# R201B.net
KiCad netlist of a schematic drawn in EAGLE
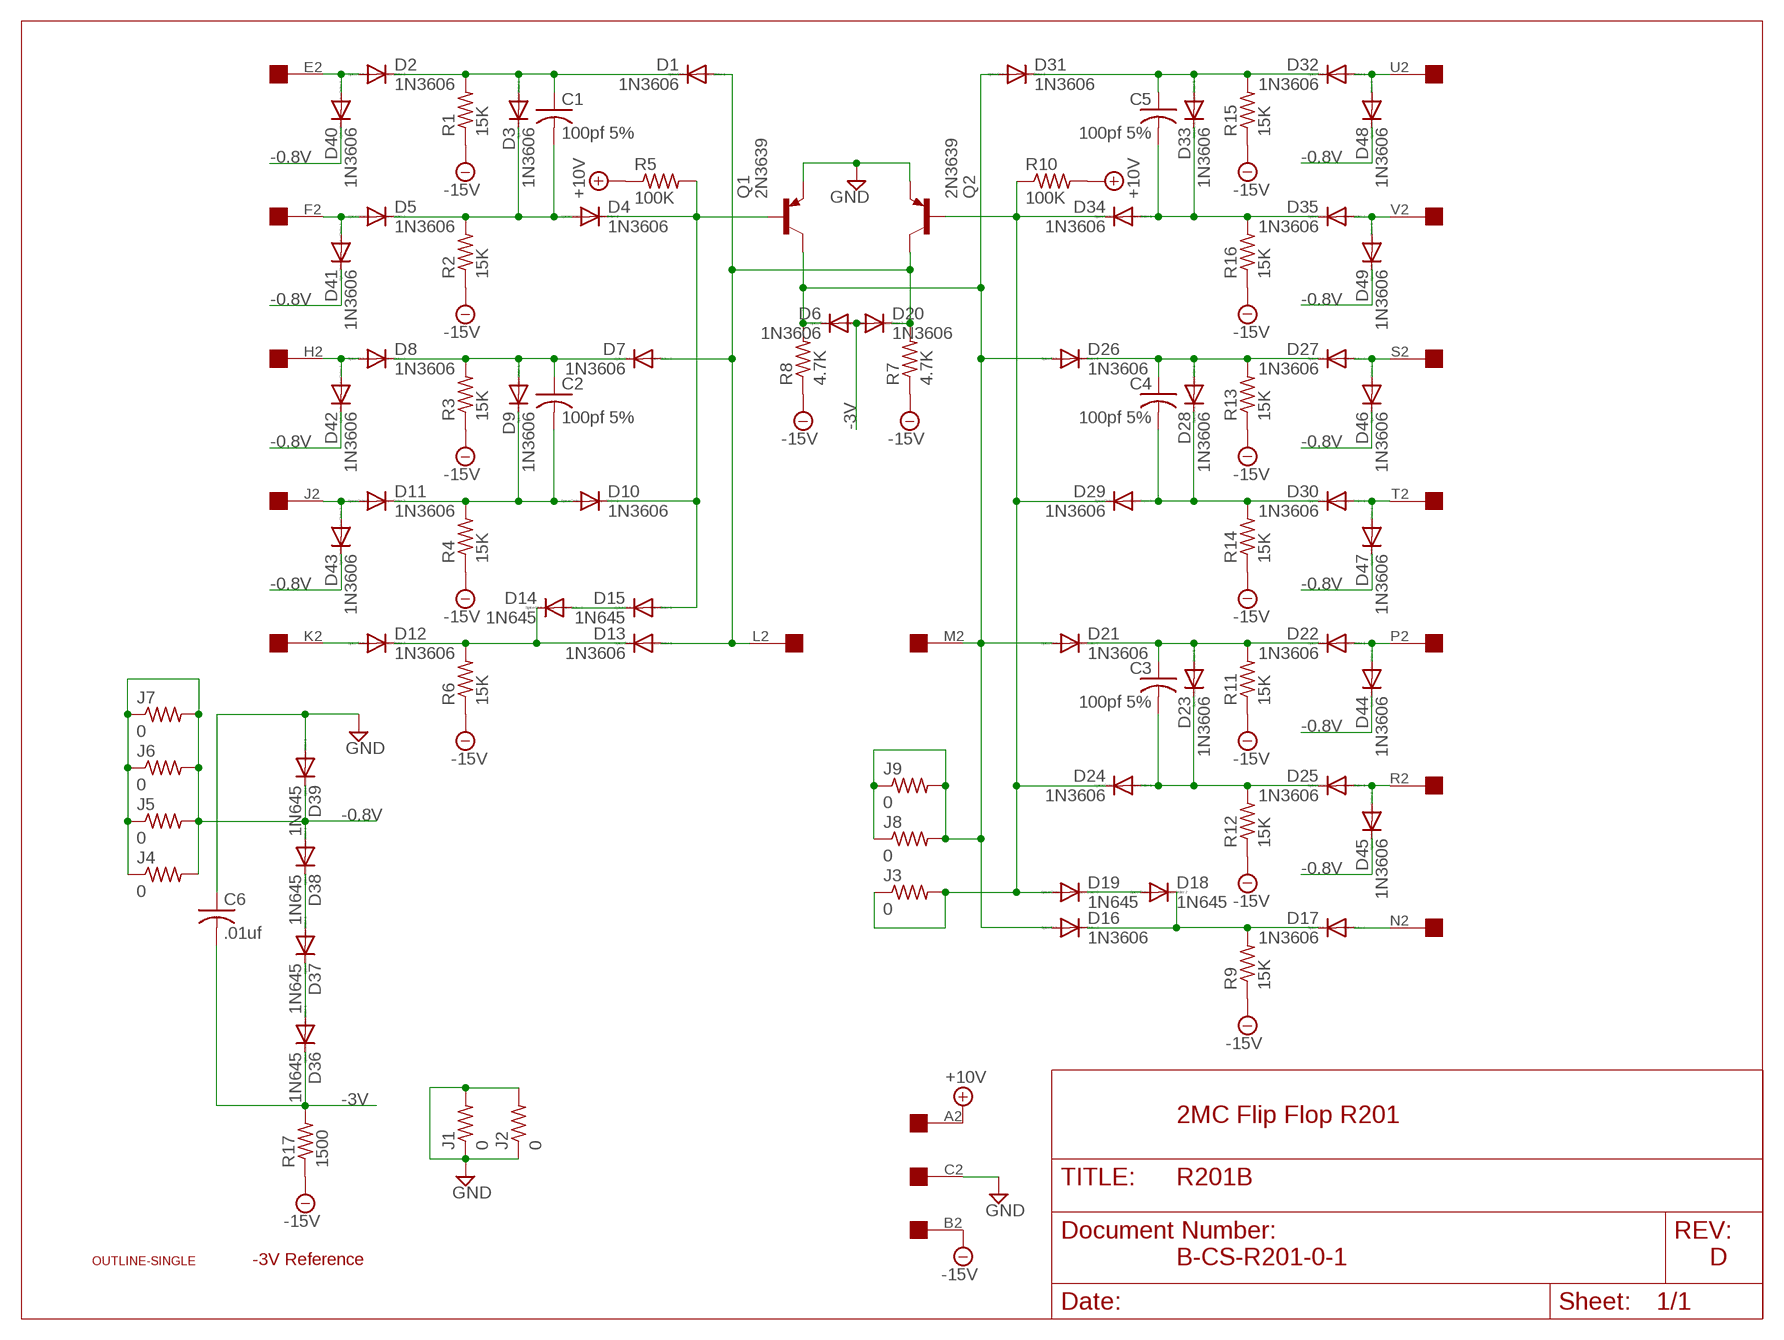
[diagram p0: schematic, sheet 1]

(export (version "E")
  (design (tool "Eeschema 10.0.6"))
  (components
    (comp (ref "C1")
      (value "100pf 5%")
      (footprint "eagle-import:C063-025X075")
      (libsource (lib "eagle-import") (part "C-US"))
    )
    (comp (ref "C2")
      (value "100pf 5%")
      (footprint "eagle-import:C063-025X075")
      (libsource (lib "eagle-import") (part "C-US"))
    )
    (comp (ref "C3")
      (value "100pf 5%")
      (footprint "eagle-import:C063-025X075")
      (libsource (lib "eagle-import") (part "C-US"))
    )
    (comp (ref "C4")
      (value "100pf 5%")
      (footprint "eagle-import:C063-025X075")
      (libsource (lib "eagle-import") (part "C-US"))
    )
    (comp (ref "C5")
      (value "100pf 5%")
      (footprint "eagle-import:C063-025X075")
      (libsource (lib "eagle-import") (part "C-US"))
    )
    (comp (ref "C6")
      (value ".01uf")
      (footprint "eagle-import:C063-025X075")
      (libsource (lib "eagle-import") (part "C-US"))
    )
    (comp (ref "D1")
      (value "1N3606")
      (footprint "eagle-import:DO35-10")
      (libsource (lib "eagle-import") (part "1N4148DO35-10"))
    )
    (comp (ref "D2")
      (value "1N3606")
      (footprint "eagle-import:DO35-10")
      (libsource (lib "eagle-import") (part "1N4148DO35-10"))
    )
    (comp (ref "D3")
      (value "1N3606")
      (footprint "eagle-import:DO35-10")
      (libsource (lib "eagle-import") (part "1N4148DO35-10"))
    )
    (comp (ref "D4")
      (value "1N3606")
      (footprint "eagle-import:DO35-10")
      (libsource (lib "eagle-import") (part "1N4148DO35-10"))
    )
    (comp (ref "D5")
      (value "1N3606")
      (footprint "eagle-import:DO35-10")
      (libsource (lib "eagle-import") (part "1N4148DO35-10"))
    )
    (comp (ref "D6")
      (value "1N3606")
      (footprint "eagle-import:DO35-10")
      (libsource (lib "eagle-import") (part "1N4148DO35-10"))
    )
    (comp (ref "D7")
      (value "1N3606")
      (footprint "eagle-import:DO35-10")
      (libsource (lib "eagle-import") (part "1N4148DO35-10"))
    )
    (comp (ref "D8")
      (value "1N3606")
      (footprint "eagle-import:DO35-10")
      (libsource (lib "eagle-import") (part "1N4148DO35-10"))
    )
    (comp (ref "D9")
      (value "1N3606")
      (footprint "eagle-import:DO35-10")
      (libsource (lib "eagle-import") (part "1N4148DO35-10"))
    )
    (comp (ref "D10")
      (value "1N3606")
      (footprint "eagle-import:DO35-10")
      (libsource (lib "eagle-import") (part "1N4148DO35-10"))
    )
    (comp (ref "D11")
      (value "1N3606")
      (footprint "eagle-import:DO35-10")
      (libsource (lib "eagle-import") (part "1N4148DO35-10"))
    )
    (comp (ref "D12")
      (value "1N3606")
      (footprint "eagle-import:DO35-10")
      (libsource (lib "eagle-import") (part "1N4148DO35-10"))
    )
    (comp (ref "D13")
      (value "1N3606")
      (footprint "eagle-import:DO35-10")
      (libsource (lib "eagle-import") (part "1N4148DO35-10"))
    )
    (comp (ref "D14")
      (value "1N645")
      (footprint "eagle-import:DO35-10")
      (libsource (lib "eagle-import") (part "1N4148DO35-10"))
    )
    (comp (ref "D15")
      (value "1N645")
      (footprint "eagle-import:DO35-10")
      (libsource (lib "eagle-import") (part "1N4148DO35-10"))
    )
    (comp (ref "D16")
      (value "1N3606")
      (footprint "eagle-import:DO35-10")
      (libsource (lib "eagle-import") (part "1N4148DO35-10"))
    )
    (comp (ref "D17")
      (value "1N3606")
      (footprint "eagle-import:DO35-10")
      (libsource (lib "eagle-import") (part "1N4148DO35-10"))
    )
    (comp (ref "D18")
      (value "1N645")
      (footprint "eagle-import:DO35-10")
      (libsource (lib "eagle-import") (part "1N4148DO35-10"))
    )
    (comp (ref "D19")
      (value "1N645")
      (footprint "eagle-import:DO35-10")
      (libsource (lib "eagle-import") (part "1N4148DO35-10"))
    )
    (comp (ref "D20")
      (value "1N3606")
      (footprint "eagle-import:DO35-10")
      (libsource (lib "eagle-import") (part "1N4148DO35-10"))
    )
    (comp (ref "D21")
      (value "1N3606")
      (footprint "eagle-import:DO35-10")
      (libsource (lib "eagle-import") (part "1N4148DO35-10"))
    )
    (comp (ref "D22")
      (value "1N3606")
      (footprint "eagle-import:DO35-10")
      (libsource (lib "eagle-import") (part "1N4148DO35-10"))
    )
    (comp (ref "D23")
      (value "1N3606")
      (footprint "eagle-import:DO35-10")
      (libsource (lib "eagle-import") (part "1N4148DO35-10"))
    )
    (comp (ref "D24")
      (value "1N3606")
      (footprint "eagle-import:DO35-10")
      (libsource (lib "eagle-import") (part "1N4148DO35-10"))
    )
    (comp (ref "D25")
      (value "1N3606")
      (footprint "eagle-import:DO35-10")
      (libsource (lib "eagle-import") (part "1N4148DO35-10"))
    )
    (comp (ref "D26")
      (value "1N3606")
      (footprint "eagle-import:DO35-10")
      (libsource (lib "eagle-import") (part "1N4148DO35-10"))
    )
    (comp (ref "D27")
      (value "1N3606")
      (footprint "eagle-import:DO35-10")
      (libsource (lib "eagle-import") (part "1N4148DO35-10"))
    )
    (comp (ref "D28")
      (value "1N3606")
      (footprint "eagle-import:DO35-10")
      (libsource (lib "eagle-import") (part "1N4148DO35-10"))
    )
    (comp (ref "D29")
      (value "1N3606")
      (footprint "eagle-import:DO35-10")
      (libsource (lib "eagle-import") (part "1N4148DO35-10"))
    )
    (comp (ref "D30")
      (value "1N3606")
      (footprint "eagle-import:DO35-10")
      (libsource (lib "eagle-import") (part "1N4148DO35-10"))
    )
    (comp (ref "D31")
      (value "1N3606")
      (footprint "eagle-import:DO35-10")
      (libsource (lib "eagle-import") (part "1N4148DO35-10"))
    )
    (comp (ref "D32")
      (value "1N3606")
      (footprint "eagle-import:DO35-10")
      (libsource (lib "eagle-import") (part "1N4148DO35-10"))
    )
    (comp (ref "D33")
      (value "1N3606")
      (footprint "eagle-import:DO35-10")
      (libsource (lib "eagle-import") (part "1N4148DO35-10"))
    )
    (comp (ref "D34")
      (value "1N3606")
      (footprint "eagle-import:DO35-10")
      (libsource (lib "eagle-import") (part "1N4148DO35-10"))
    )
    (comp (ref "D35")
      (value "1N3606")
      (footprint "eagle-import:DO35-10")
      (libsource (lib "eagle-import") (part "1N4148DO35-10"))
    )
    (comp (ref "D36")
      (value "1N645")
      (footprint "eagle-import:DO35-10")
      (libsource (lib "eagle-import") (part "1N4148DO35-10"))
    )
    (comp (ref "D37")
      (value "1N645")
      (footprint "eagle-import:DO35-10")
      (libsource (lib "eagle-import") (part "1N4148DO35-10"))
    )
    (comp (ref "D38")
      (value "1N645")
      (footprint "eagle-import:DO35-10")
      (libsource (lib "eagle-import") (part "1N4148DO35-10"))
    )
    (comp (ref "D39")
      (value "1N645")
      (footprint "eagle-import:DO35-10")
      (libsource (lib "eagle-import") (part "1N4148DO35-10"))
    )
    (comp (ref "D40")
      (value "1N3606")
      (footprint "eagle-import:DO35-10")
      (libsource (lib "eagle-import") (part "1N4148DO35-10"))
    )
    (comp (ref "D41")
      (value "1N3606")
      (footprint "eagle-import:DO35-10")
      (libsource (lib "eagle-import") (part "1N4148DO35-10"))
    )
    (comp (ref "D42")
      (value "1N3606")
      (footprint "eagle-import:DO35-10")
      (libsource (lib "eagle-import") (part "1N4148DO35-10"))
    )
    (comp (ref "D43")
      (value "1N3606")
      (footprint "eagle-import:DO35-10")
      (libsource (lib "eagle-import") (part "1N4148DO35-10"))
    )
    (comp (ref "D44")
      (value "1N3606")
      (footprint "eagle-import:DO35-10")
      (libsource (lib "eagle-import") (part "1N4148DO35-10"))
    )
    (comp (ref "D45")
      (value "1N3606")
      (footprint "eagle-import:DO35-10")
      (libsource (lib "eagle-import") (part "1N4148DO35-10"))
    )
    (comp (ref "D46")
      (value "1N3606")
      (footprint "eagle-import:DO35-10")
      (libsource (lib "eagle-import") (part "1N4148DO35-10"))
    )
    (comp (ref "D47")
      (value "1N3606")
      (footprint "eagle-import:DO35-10")
      (libsource (lib "eagle-import") (part "1N4148DO35-10"))
    )
    (comp (ref "D48")
      (value "1N3606")
      (footprint "eagle-import:DO35-10")
      (libsource (lib "eagle-import") (part "1N4148DO35-10"))
    )
    (comp (ref "D49")
      (value "1N3606")
      (footprint "eagle-import:DO35-10")
      (libsource (lib "eagle-import") (part "1N4148DO35-10"))
    )
    (comp (ref "J1")
      (value "0")
      (footprint "eagle-import:0207_10")
      (libsource (lib "eagle-import") (part "R-US_0207/10"))
    )
    (comp (ref "J2")
      (value "0")
      (footprint "eagle-import:0207_10")
      (libsource (lib "eagle-import") (part "R-US_0207/10"))
    )
    (comp (ref "J3")
      (value "0")
      (footprint "eagle-import:0207_10")
      (libsource (lib "eagle-import") (part "R-US_0207/10"))
    )
    (comp (ref "J4")
      (value "0")
      (footprint "eagle-import:0207_10")
      (libsource (lib "eagle-import") (part "R-US_0207/10"))
    )
    (comp (ref "J5")
      (value "0")
      (footprint "eagle-import:0207_10")
      (libsource (lib "eagle-import") (part "R-US_0207/10"))
    )
    (comp (ref "J6")
      (value "0")
      (footprint "eagle-import:0207_10")
      (libsource (lib "eagle-import") (part "R-US_0207/10"))
    )
    (comp (ref "J7")
      (value "0")
      (footprint "eagle-import:0207_10")
      (libsource (lib "eagle-import") (part "R-US_0207/10"))
    )
    (comp (ref "J8")
      (value "0")
      (footprint "eagle-import:0207_10")
      (libsource (lib "eagle-import") (part "R-US_0207/10"))
    )
    (comp (ref "J9")
      (value "0")
      (footprint "eagle-import:0207_10")
      (libsource (lib "eagle-import") (part "R-US_0207/10"))
    )
    (comp (ref "Q1")
      (value "2N3639")
      (footprint "eagle-import:TO39")
      (libsource (lib "eagle-import") (part "2N3637"))
    )
    (comp (ref "Q2")
      (value "2N3639")
      (footprint "eagle-import:TO39")
      (libsource (lib "eagle-import") (part "2N3637"))
    )
    (comp (ref "R1")
      (value "15K")
      (footprint "eagle-import:0207_10")
      (libsource (lib "eagle-import") (part "R-US_0207/10"))
    )
    (comp (ref "R2")
      (value "15K")
      (footprint "eagle-import:0207_10")
      (libsource (lib "eagle-import") (part "R-US_0207/10"))
    )
    (comp (ref "R3")
      (value "15K")
      (footprint "eagle-import:0207_10")
      (libsource (lib "eagle-import") (part "R-US_0207/10"))
    )
    (comp (ref "R4")
      (value "15K")
      (footprint "eagle-import:0207_10")
      (libsource (lib "eagle-import") (part "R-US_0207/10"))
    )
    (comp (ref "R5")
      (value "100K")
      (footprint "eagle-import:0207_10")
      (libsource (lib "eagle-import") (part "R-US_0207/10"))
    )
    (comp (ref "R6")
      (value "15K")
      (footprint "eagle-import:0207_10")
      (libsource (lib "eagle-import") (part "R-US_0207/10"))
    )
    (comp (ref "R7")
      (value "4.7K")
      (footprint "eagle-import:0207_10")
      (libsource (lib "eagle-import") (part "R-US_0207/10"))
    )
    (comp (ref "R8")
      (value "4.7K")
      (footprint "eagle-import:0207_10")
      (libsource (lib "eagle-import") (part "R-US_0207/10"))
    )
    (comp (ref "R9")
      (value "15K")
      (footprint "eagle-import:0207_10")
      (libsource (lib "eagle-import") (part "R-US_0207/10"))
    )
    (comp (ref "R10")
      (value "100K")
      (footprint "eagle-import:0207_10")
      (libsource (lib "eagle-import") (part "R-US_0207/10"))
    )
    (comp (ref "R11")
      (value "15K")
      (footprint "eagle-import:0207_10")
      (libsource (lib "eagle-import") (part "R-US_0207/10"))
    )
    (comp (ref "R12")
      (value "15K")
      (footprint "eagle-import:0207_10")
      (libsource (lib "eagle-import") (part "R-US_0207/10"))
    )
    (comp (ref "R13")
      (value "15K")
      (footprint "eagle-import:0207_10")
      (libsource (lib "eagle-import") (part "R-US_0207/10"))
    )
    (comp (ref "R14")
      (value "15K")
      (footprint "eagle-import:0207_10")
      (libsource (lib "eagle-import") (part "R-US_0207/10"))
    )
    (comp (ref "R15")
      (value "15K")
      (footprint "eagle-import:0207_10")
      (libsource (lib "eagle-import") (part "R-US_0207/10"))
    )
    (comp (ref "R16")
      (value "15K")
      (footprint "eagle-import:0207_10")
      (libsource (lib "eagle-import") (part "R-US_0207/10"))
    )
    (comp (ref "R17")
      (value "1500")
      (footprint "eagle-import:0207_10")
      (libsource (lib "eagle-import") (part "R-US_0207/10"))
    )
    (comp (ref "U$1")
      (value "OUTLINE-SINGLE")
      (footprint "eagle-import:SINGLE")
      (libsource (lib "eagle-import") (part "OUTLINE-SINGLE"))
    )
    (comp (ref "U$2")
      (value "EDGE-1")
      (footprint "eagle-import:EDGE-CON1")
      (libsource (lib "eagle-import") (part "EDGE-1"))
    )
  )
  (nets
    (net (code "1") (name "+10V") (class "Default")
      (node (ref "R10") (pin "2") (pinfunction "2_2") (pintype "passive"))
      (node (ref "R5") (pin "1") (pinfunction "1_1") (pintype "passive"))
      (node (ref "U$2") (pin "A2") (pinfunction "1_A2") (pintype "bidirectional"))
    )
    (net (code "2") (name "-15V") (class "Default")
      (node (ref "R1") (pin "1") (pinfunction "1_1") (pintype "passive"))
      (node (ref "R11") (pin "1") (pinfunction "1_1") (pintype "passive"))
      (node (ref "R12") (pin "1") (pinfunction "1_1") (pintype "passive"))
      (node (ref "R13") (pin "1") (pinfunction "1_1") (pintype "passive"))
      (node (ref "R14") (pin "1") (pinfunction "1_1") (pintype "passive"))
      (node (ref "R15") (pin "1") (pinfunction "1_1") (pintype "passive"))
      (node (ref "R16") (pin "1") (pinfunction "1_1") (pintype "passive"))
      (node (ref "R17") (pin "1") (pinfunction "1_1") (pintype "passive"))
      (node (ref "R2") (pin "1") (pinfunction "1_1") (pintype "passive"))
      (node (ref "R3") (pin "1") (pinfunction "1_1") (pintype "passive"))
      (node (ref "R4") (pin "1") (pinfunction "1_1") (pintype "passive"))
      (node (ref "R6") (pin "1") (pinfunction "1_1") (pintype "passive"))
      (node (ref "R7") (pin "1") (pinfunction "1_1") (pintype "passive"))
      (node (ref "R8") (pin "1") (pinfunction "1_1") (pintype "passive"))
      (node (ref "R9") (pin "1") (pinfunction "1_1") (pintype "passive"))
      (node (ref "U$2") (pin "B2") (pinfunction "1_B2") (pintype "bidirectional"))
    )
    (net (code "3") (name "/-0.8V") (class "Default")
      (node (ref "D38") (pin "A") (pinfunction "A_A") (pintype "passive"))
      (node (ref "D39") (pin "C") (pinfunction "C_C") (pintype "passive"))
      (node (ref "D40") (pin "C") (pinfunction "C_C") (pintype "passive"))
      (node (ref "D41") (pin "C") (pinfunction "C_C") (pintype "passive"))
      (node (ref "D42") (pin "C") (pinfunction "C_C") (pintype "passive"))
      (node (ref "D43") (pin "C") (pinfunction "C_C") (pintype "passive"))
      (node (ref "D44") (pin "C") (pinfunction "C_C") (pintype "passive"))
      (node (ref "D45") (pin "C") (pinfunction "C_C") (pintype "passive"))
      (node (ref "D46") (pin "C") (pinfunction "C_C") (pintype "passive"))
      (node (ref "D47") (pin "C") (pinfunction "C_C") (pintype "passive"))
      (node (ref "D48") (pin "C") (pinfunction "C_C") (pintype "passive"))
      (node (ref "D49") (pin "C") (pinfunction "C_C") (pintype "passive"))
      (node (ref "J4") (pin "1") (pinfunction "1_1") (pintype "passive"))
      (node (ref "J4") (pin "2") (pinfunction "2_2") (pintype "passive"))
      (node (ref "J5") (pin "1") (pinfunction "1_1") (pintype "passive"))
      (node (ref "J5") (pin "2") (pinfunction "2_2") (pintype "passive"))
      (node (ref "J6") (pin "1") (pinfunction "1_1") (pintype "passive"))
      (node (ref "J6") (pin "2") (pinfunction "2_2") (pintype "passive"))
      (node (ref "J7") (pin "1") (pinfunction "1_1") (pintype "passive"))
      (node (ref "J7") (pin "2") (pinfunction "2_2") (pintype "passive"))
    )
    (net (code "4") (name "/-3V") (class "Default")
      (node (ref "C6") (pin "2") (pinfunction "2_2") (pintype "passive"))
      (node (ref "D20") (pin "A") (pinfunction "A_A") (pintype "passive"))
      (node (ref "D36") (pin "C") (pinfunction "C_C") (pintype "passive"))
      (node (ref "D6") (pin "A") (pinfunction "A_A") (pintype "passive"))
      (node (ref "R17") (pin "2") (pinfunction "2_2") (pintype "passive"))
    )
    (net (code "5") (name "GND") (class "Default")
      (node (ref "C6") (pin "1") (pinfunction "1_1") (pintype "passive"))
      (node (ref "D39") (pin "A") (pinfunction "A_A") (pintype "passive"))
      (node (ref "J1") (pin "1") (pinfunction "1_1") (pintype "passive"))
      (node (ref "J1") (pin "2") (pinfunction "2_2") (pintype "passive"))
      (node (ref "J2") (pin "1") (pinfunction "1_1") (pintype "passive"))
      (node (ref "J2") (pin "2") (pinfunction "2_2") (pintype "passive"))
      (node (ref "Q1") (pin "1") (pinfunction "E_1") (pintype "passive"))
      (node (ref "Q2") (pin "1") (pinfunction "E_1") (pintype "passive"))
      (node (ref "U$2") (pin "C2") (pinfunction "1_C2") (pintype "bidirectional"))
    )
    (net (code "6") (name "Net-(C1-Pad1)") (class "Default")
      (node (ref "C1") (pin "1") (pinfunction "1_1") (pintype "passive"))
      (node (ref "D1") (pin "C") (pinfunction "C_C") (pintype "passive"))
      (node (ref "D2") (pin "C") (pinfunction "C_C") (pintype "passive"))
      (node (ref "D3") (pin "A") (pinfunction "A_A") (pintype "passive"))
      (node (ref "R1") (pin "2") (pinfunction "2_2") (pintype "passive"))
    )
    (net (code "7") (name "Net-(C1-Pad2)") (class "Default")
      (node (ref "C1") (pin "2") (pinfunction "2_2") (pintype "passive"))
      (node (ref "D3") (pin "C") (pinfunction "C_C") (pintype "passive"))
      (node (ref "D4") (pin "A") (pinfunction "A_A") (pintype "passive"))
      (node (ref "D5") (pin "C") (pinfunction "C_C") (pintype "passive"))
      (node (ref "R2") (pin "2") (pinfunction "2_2") (pintype "passive"))
    )
    (net (code "8") (name "Net-(C2-Pad1)") (class "Default")
      (node (ref "C2") (pin "1") (pinfunction "1_1") (pintype "passive"))
      (node (ref "D7") (pin "C") (pinfunction "C_C") (pintype "passive"))
      (node (ref "D8") (pin "C") (pinfunction "C_C") (pintype "passive"))
      (node (ref "D9") (pin "A") (pinfunction "A_A") (pintype "passive"))
      (node (ref "R3") (pin "2") (pinfunction "2_2") (pintype "passive"))
    )
    (net (code "9") (name "Net-(C2-Pad2)") (class "Default")
      (node (ref "C2") (pin "2") (pinfunction "2_2") (pintype "passive"))
      (node (ref "D10") (pin "A") (pinfunction "A_A") (pintype "passive"))
      (node (ref "D11") (pin "C") (pinfunction "C_C") (pintype "passive"))
      (node (ref "D9") (pin "C") (pinfunction "C_C") (pintype "passive"))
      (node (ref "R4") (pin "2") (pinfunction "2_2") (pintype "passive"))
    )
    (net (code "10") (name "Net-(C3-Pad1)") (class "Default")
      (node (ref "C3") (pin "1") (pinfunction "1_1") (pintype "passive"))
      (node (ref "D21") (pin "C") (pinfunction "C_C") (pintype "passive"))
      (node (ref "D22") (pin "C") (pinfunction "C_C") (pintype "passive"))
      (node (ref "D23") (pin "A") (pinfunction "A_A") (pintype "passive"))
      (node (ref "R11") (pin "2") (pinfunction "2_2") (pintype "passive"))
    )
    (net (code "11") (name "Net-(C3-Pad2)") (class "Default")
      (node (ref "C3") (pin "2") (pinfunction "2_2") (pintype "passive"))
      (node (ref "D23") (pin "C") (pinfunction "C_C") (pintype "passive"))
      (node (ref "D24") (pin "A") (pinfunction "A_A") (pintype "passive"))
      (node (ref "D25") (pin "C") (pinfunction "C_C") (pintype "passive"))
      (node (ref "R12") (pin "2") (pinfunction "2_2") (pintype "passive"))
    )
    (net (code "12") (name "Net-(C4-Pad1)") (class "Default")
      (node (ref "C4") (pin "1") (pinfunction "1_1") (pintype "passive"))
      (node (ref "D26") (pin "C") (pinfunction "C_C") (pintype "passive"))
      (node (ref "D27") (pin "C") (pinfunction "C_C") (pintype "passive"))
      (node (ref "D28") (pin "A") (pinfunction "A_A") (pintype "passive"))
      (node (ref "R13") (pin "2") (pinfunction "2_2") (pintype "passive"))
    )
    (net (code "13") (name "Net-(C4-Pad2)") (class "Default")
      (node (ref "C4") (pin "2") (pinfunction "2_2") (pintype "passive"))
      (node (ref "D28") (pin "C") (pinfunction "C_C") (pintype "passive"))
      (node (ref "D29") (pin "A") (pinfunction "A_A") (pintype "passive"))
      (node (ref "D30") (pin "C") (pinfunction "C_C") (pintype "passive"))
      (node (ref "R14") (pin "2") (pinfunction "2_2") (pintype "passive"))
    )
    (net (code "14") (name "Net-(C5-Pad1)") (class "Default")
      (node (ref "C5") (pin "1") (pinfunction "1_1") (pintype "passive"))
      (node (ref "D31") (pin "C") (pinfunction "C_C") (pintype "passive"))
      (node (ref "D32") (pin "C") (pinfunction "C_C") (pintype "passive"))
      (node (ref "D33") (pin "A") (pinfunction "A_A") (pintype "passive"))
      (node (ref "R15") (pin "2") (pinfunction "2_2") (pintype "passive"))
    )
    (net (code "15") (name "Net-(C5-Pad2)") (class "Default")
      (node (ref "C5") (pin "2") (pinfunction "2_2") (pintype "passive"))
      (node (ref "D33") (pin "C") (pinfunction "C_C") (pintype "passive"))
      (node (ref "D34") (pin "A") (pinfunction "A_A") (pintype "passive"))
      (node (ref "D35") (pin "C") (pinfunction "C_C") (pintype "passive"))
      (node (ref "R16") (pin "2") (pinfunction "2_2") (pintype "passive"))
    )
    (net (code "16") (name "Net-(D12-PadC)") (class "Default")
      (node (ref "D12") (pin "C") (pinfunction "C_C") (pintype "passive"))
      (node (ref "D13") (pin "C") (pinfunction "C_C") (pintype "passive"))
      (node (ref "D14") (pin "C") (pinfunction "C_C") (pintype "passive"))
      (node (ref "R6") (pin "2") (pinfunction "2_2") (pintype "passive"))
    )
    (net (code "17") (name "Net-(D14-PadA)") (class "Default")
      (node (ref "D14") (pin "A") (pinfunction "A_A") (pintype "passive"))
      (node (ref "D15") (pin "C") (pinfunction "C_C") (pintype "passive"))
    )
    (net (code "18") (name "Net-(D16-PadC)") (class "Default")
      (node (ref "D16") (pin "C") (pinfunction "C_C") (pintype "passive"))
      (node (ref "D17") (pin "C") (pinfunction "C_C") (pintype "passive"))
      (node (ref "D18") (pin "C") (pinfunction "C_C") (pintype "passive"))
      (node (ref "R9") (pin "2") (pinfunction "2_2") (pintype "passive"))
    )
    (net (code "19") (name "Net-(D18-PadA)") (class "Default")
      (node (ref "D18") (pin "A") (pinfunction "A_A") (pintype "passive"))
      (node (ref "D19") (pin "C") (pinfunction "C_C") (pintype "passive"))
    )
    (net (code "20") (name "Net-(D36-PadA)") (class "Default")
      (node (ref "D36") (pin "A") (pinfunction "A_A") (pintype "passive"))
      (node (ref "D37") (pin "C") (pinfunction "C_C") (pintype "passive"))
    )
    (net (code "21") (name "Net-(D37-PadA)") (class "Default")
      (node (ref "D37") (pin "A") (pinfunction "A_A") (pintype "passive"))
      (node (ref "D38") (pin "C") (pinfunction "C_C") (pintype "passive"))
    )
    (net (code "22") (name "Net-(Q1-B)") (class "Default")
      (node (ref "D10") (pin "C") (pinfunction "C_C") (pintype "passive"))
      (node (ref "D15") (pin "A") (pinfunction "A_A") (pintype "passive"))
      (node (ref "D4") (pin "C") (pinfunction "C_C") (pintype "passive"))
      (node (ref "Q1") (pin "2") (pinfunction "B_2") (pintype "passive"))
      (node (ref "R5") (pin "2") (pinfunction "2_2") (pintype "passive"))
    )
    (net (code "23") (name "Net-(Q1-C)") (class "Default")
      (node (ref "D16") (pin "A") (pinfunction "A_A") (pintype "passive"))
      (node (ref "D21") (pin "A") (pinfunction "A_A") (pintype "passive"))
      (node (ref "D26") (pin "A") (pinfunction "A_A") (pintype "passive"))
      (node (ref "D31") (pin "A") (pinfunction "A_A") (pintype "passive"))
      (node (ref "D6") (pin "C") (pinfunction "C_C") (pintype "passive"))
      (node (ref "J8") (pin "1") (pinfunction "1_1") (pintype "passive"))
      (node (ref "J8") (pin "2") (pinfunction "2_2") (pintype "passive"))
      (node (ref "J9") (pin "1") (pinfunction "1_1") (pintype "passive"))
      (node (ref "J9") (pin "2") (pinfunction "2_2") (pintype "passive"))
      (node (ref "Q1") (pin "3") (pinfunction "C_3") (pintype "passive"))
      (node (ref "R8") (pin "2") (pinfunction "2_2") (pintype "passive"))
      (node (ref "U$2") (pin "M2") (pinfunction "1_M2") (pintype "bidirectional"))
    )
    (net (code "24") (name "Net-(Q2-B)") (class "Default")
      (node (ref "D19") (pin "A") (pinfunction "A_A") (pintype "passive"))
      (node (ref "D24") (pin "C") (pinfunction "C_C") (pintype "passive"))
      (node (ref "D29") (pin "C") (pinfunction "C_C") (pintype "passive"))
      (node (ref "D34") (pin "C") (pinfunction "C_C") (pintype "passive"))
      (node (ref "J3") (pin "1") (pinfunction "1_1") (pintype "passive"))
      (node (ref "J3") (pin "2") (pinfunction "2_2") (pintype "passive"))
      (node (ref "Q2") (pin "2") (pinfunction "B_2") (pintype "passive"))
      (node (ref "R10") (pin "1") (pinfunction "1_1") (pintype "passive"))
    )
    (net (code "25") (name "Net-(Q2-C)") (class "Default")
      (node (ref "D1") (pin "A") (pinfunction "A_A") (pintype "passive"))
      (node (ref "D13") (pin "A") (pinfunction "A_A") (pintype "passive"))
      (node (ref "D20") (pin "C") (pinfunction "C_C") (pintype "passive"))
      (node (ref "D7") (pin "A") (pinfunction "A_A") (pintype "passive"))
      (node (ref "Q2") (pin "3") (pinfunction "C_3") (pintype "passive"))
      (node (ref "R7") (pin "2") (pinfunction "2_2") (pintype "passive"))
      (node (ref "U$2") (pin "L2") (pinfunction "1_L2") (pintype "bidirectional"))
    )
    (net (code "26") (name "Net-(U$2E-1)") (class "Default")
      (node (ref "D2") (pin "A") (pinfunction "A_A") (pintype "passive"))
      (node (ref "D40") (pin "A") (pinfunction "A_A") (pintype "passive"))
      (node (ref "U$2") (pin "E2") (pinfunction "1_E2") (pintype "bidirectional"))
    )
    (net (code "27") (name "Net-(U$2F-1)") (class "Default")
      (node (ref "D41") (pin "A") (pinfunction "A_A") (pintype "passive"))
      (node (ref "D5") (pin "A") (pinfunction "A_A") (pintype "passive"))
      (node (ref "U$2") (pin "F2") (pinfunction "1_F2") (pintype "bidirectional"))
    )
    (net (code "28") (name "Net-(U$2G-1)") (class "Default")
      (node (ref "D42") (pin "A") (pinfunction "A_A") (pintype "passive"))
      (node (ref "D8") (pin "A") (pinfunction "A_A") (pintype "passive"))
      (node (ref "U$2") (pin "H2") (pinfunction "1_H2") (pintype "bidirectional"))
    )
    (net (code "29") (name "Net-(U$2H-1)") (class "Default")
      (node (ref "D11") (pin "A") (pinfunction "A_A") (pintype "passive"))
      (node (ref "D43") (pin "A") (pinfunction "A_A") (pintype "passive"))
      (node (ref "U$2") (pin "J2") (pinfunction "1_J2") (pintype "bidirectional"))
    )
    (net (code "30") (name "Net-(U$2I-1)") (class "Default")
      (node (ref "D12") (pin "A") (pinfunction "A_A") (pintype "passive"))
      (node (ref "U$2") (pin "K2") (pinfunction "1_K2") (pintype "bidirectional"))
    )
    (net (code "31") (name "Net-(U$2L-1)") (class "Default")
      (node (ref "D17") (pin "A") (pinfunction "A_A") (pintype "passive"))
      (node (ref "U$2") (pin "N2") (pinfunction "1_N2") (pintype "bidirectional"))
    )
    (net (code "32") (name "Net-(U$2M-1)") (class "Default")
      (node (ref "D22") (pin "A") (pinfunction "A_A") (pintype "passive"))
      (node (ref "D44") (pin "A") (pinfunction "A_A") (pintype "passive"))
      (node (ref "U$2") (pin "P2") (pinfunction "1_P2") (pintype "bidirectional"))
    )
    (net (code "33") (name "Net-(U$2N-1)") (class "Default")
      (node (ref "D25") (pin "A") (pinfunction "A_A") (pintype "passive"))
      (node (ref "D45") (pin "A") (pinfunction "A_A") (pintype "passive"))
      (node (ref "U$2") (pin "R2") (pinfunction "1_R2") (pintype "bidirectional"))
    )
    (net (code "34") (name "Net-(U$2O-1)") (class "Default")
      (node (ref "D27") (pin "A") (pinfunction "A_A") (pintype "passive"))
      (node (ref "D46") (pin "A") (pinfunction "A_A") (pintype "passive"))
      (node (ref "U$2") (pin "S2") (pinfunction "1_S2") (pintype "bidirectional"))
    )
    (net (code "35") (name "Net-(U$2P-1)") (class "Default")
      (node (ref "D30") (pin "A") (pinfunction "A_A") (pintype "passive"))
      (node (ref "D47") (pin "A") (pinfunction "A_A") (pintype "passive"))
      (node (ref "U$2") (pin "T2") (pinfunction "1_T2") (pintype "bidirectional"))
    )
    (net (code "36") (name "Net-(U$2Q-1)") (class "Default")
      (node (ref "D32") (pin "A") (pinfunction "A_A") (pintype "passive"))
      (node (ref "D48") (pin "A") (pinfunction "A_A") (pintype "passive"))
      (node (ref "U$2") (pin "U2") (pinfunction "1_U2") (pintype "bidirectional"))
    )
    (net (code "37") (name "Net-(U$2R-1)") (class "Default")
      (node (ref "D35") (pin "A") (pinfunction "A_A") (pintype "passive"))
      (node (ref "D49") (pin "A") (pinfunction "A_A") (pintype "passive"))
      (node (ref "U$2") (pin "V2") (pinfunction "1_V2") (pintype "bidirectional"))
    )
  )
)
